# JonesHBridge.net
KiCad netlist of a schematic drawn in EAGLE
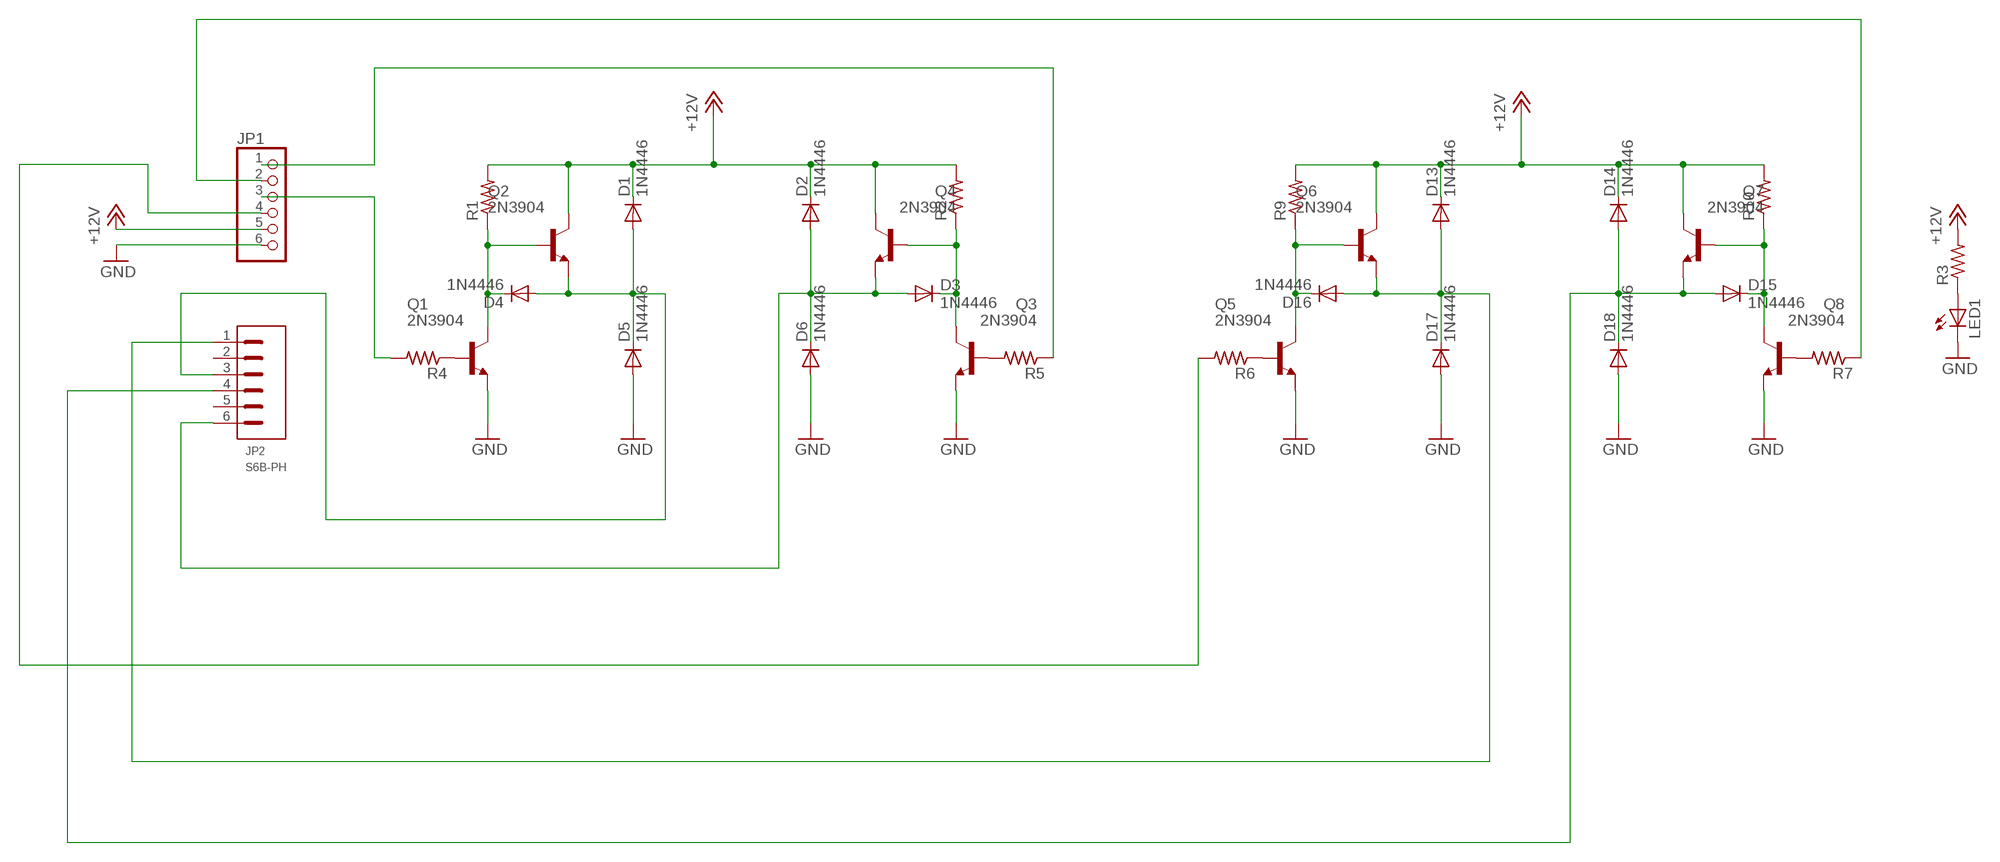
[diagram p0: schematic, sheet 1]

(export (version "E")
  (design (tool "Eeschema 10.0.6"))
  (components
    (comp (ref "D1")
      (value "1N4446")
      (footprint "eagle-import:DO35-10")
      (libsource (lib "eagle-import") (part "1N4446"))
    )
    (comp (ref "D2")
      (value "1N4446")
      (footprint "eagle-import:DO35-10")
      (libsource (lib "eagle-import") (part "1N4446"))
    )
    (comp (ref "D3")
      (value "1N4446")
      (footprint "eagle-import:DO35-10")
      (libsource (lib "eagle-import") (part "1N4446"))
    )
    (comp (ref "D4")
      (value "1N4446")
      (footprint "eagle-import:DO35-10")
      (libsource (lib "eagle-import") (part "1N4446"))
    )
    (comp (ref "D5")
      (value "1N4446")
      (footprint "eagle-import:DO35-10")
      (libsource (lib "eagle-import") (part "1N4446"))
    )
    (comp (ref "D6")
      (value "1N4446")
      (footprint "eagle-import:DO35-10")
      (libsource (lib "eagle-import") (part "1N4446"))
    )
    (comp (ref "D13")
      (value "1N4446")
      (footprint "eagle-import:DO35-10")
      (libsource (lib "eagle-import") (part "1N4446"))
    )
    (comp (ref "D14")
      (value "1N4446")
      (footprint "eagle-import:DO35-10")
      (libsource (lib "eagle-import") (part "1N4446"))
    )
    (comp (ref "D15")
      (value "1N4446")
      (footprint "eagle-import:DO35-10")
      (libsource (lib "eagle-import") (part "1N4446"))
    )
    (comp (ref "D16")
      (value "1N4446")
      (footprint "eagle-import:DO35-10")
      (libsource (lib "eagle-import") (part "1N4446"))
    )
    (comp (ref "D17")
      (value "1N4446")
      (footprint "eagle-import:DO35-10")
      (libsource (lib "eagle-import") (part "1N4446"))
    )
    (comp (ref "D18")
      (value "1N4446")
      (footprint "eagle-import:DO35-10")
      (libsource (lib "eagle-import") (part "1N4446"))
    )
    (comp (ref "JP1")
      (value "PINHD-1X6")
      (footprint "eagle-import:1X06")
      (libsource (lib "eagle-import") (part "PINHD-1X6"))
    )
    (comp (ref "JP2")
      (value "S6B-PH")
      (footprint "eagle-import:S6B")
      (libsource (lib "eagle-import") (part "S6B-PH"))
    )
    (comp (ref "LED1")
      (value "LED3MM")
      (footprint "eagle-import:LED3MM")
      (libsource (lib "eagle-import") (part "LED3MM"))
    )
    (comp (ref "Q1")
      (value "2N3904")
      (footprint "eagle-import:TO92")
      (libsource (lib "eagle-import") (part "2N3904"))
    )
    (comp (ref "Q2")
      (value "2N3904")
      (footprint "eagle-import:TO92")
      (libsource (lib "eagle-import") (part "2N3904"))
    )
    (comp (ref "Q3")
      (value "2N3904")
      (footprint "eagle-import:TO92")
      (libsource (lib "eagle-import") (part "2N3904"))
    )
    (comp (ref "Q4")
      (value "2N3904")
      (footprint "eagle-import:TO92")
      (libsource (lib "eagle-import") (part "2N3904"))
    )
    (comp (ref "Q5")
      (value "2N3904")
      (footprint "eagle-import:TO92")
      (libsource (lib "eagle-import") (part "2N3904"))
    )
    (comp (ref "Q6")
      (value "2N3904")
      (footprint "eagle-import:TO92")
      (libsource (lib "eagle-import") (part "2N3904"))
    )
    (comp (ref "Q7")
      (value "2N3904")
      (footprint "eagle-import:TO92")
      (libsource (lib "eagle-import") (part "2N3904"))
    )
    (comp (ref "Q8")
      (value "2N3904")
      (footprint "eagle-import:TO92")
      (libsource (lib "eagle-import") (part "2N3904"))
    )
    (comp (ref "R1")
      (value "R-US_R0805")
      (footprint "eagle-import:R0805")
      (libsource (lib "eagle-import") (part "R-US_R0805"))
    )
    (comp (ref "R2")
      (value "R-US_R0805")
      (footprint "eagle-import:R0805")
      (libsource (lib "eagle-import") (part "R-US_R0805"))
    )
    (comp (ref "R3")
      (value "R-US_R0805")
      (footprint "eagle-import:R0805")
      (libsource (lib "eagle-import") (part "R-US_R0805"))
    )
    (comp (ref "R4")
      (value "R-US_R0805")
      (footprint "eagle-import:R0805")
      (libsource (lib "eagle-import") (part "R-US_R0805"))
    )
    (comp (ref "R5")
      (value "R-US_R0805")
      (footprint "eagle-import:R0805")
      (libsource (lib "eagle-import") (part "R-US_R0805"))
    )
    (comp (ref "R6")
      (value "R-US_R0805")
      (footprint "eagle-import:R0805")
      (libsource (lib "eagle-import") (part "R-US_R0805"))
    )
    (comp (ref "R7")
      (value "R-US_R0805")
      (footprint "eagle-import:R0805")
      (libsource (lib "eagle-import") (part "R-US_R0805"))
    )
    (comp (ref "R9")
      (value "R-US_R0805")
      (footprint "eagle-import:R0805")
      (libsource (lib "eagle-import") (part "R-US_R0805"))
    )
    (comp (ref "R10")
      (value "R-US_R0805")
      (footprint "eagle-import:R0805")
      (libsource (lib "eagle-import") (part "R-US_R0805"))
    )
  )
  (nets
    (net (code "1") (name "+12V") (class "Default")
      (node (ref "D1") (pin "C") (pinfunction "C_C") (pintype "passive"))
      (node (ref "D13") (pin "C") (pinfunction "C_C") (pintype "passive"))
      (node (ref "D14") (pin "C") (pinfunction "C_C") (pintype "passive"))
      (node (ref "D2") (pin "C") (pinfunction "C_C") (pintype "passive"))
      (node (ref "JP1") (pin "5") (pinfunction "5_5") (pintype "passive"))
      (node (ref "Q2") (pin "1") (pinfunction "C_1") (pintype "passive"))
      (node (ref "Q4") (pin "1") (pinfunction "C_1") (pintype "passive"))
      (node (ref "Q6") (pin "1") (pinfunction "C_1") (pintype "passive"))
      (node (ref "Q7") (pin "1") (pinfunction "C_1") (pintype "passive"))
      (node (ref "R1") (pin "2") (pinfunction "2_2") (pintype "passive"))
      (node (ref "R10") (pin "2") (pinfunction "2_2") (pintype "passive"))
      (node (ref "R2") (pin "2") (pinfunction "2_2") (pintype "passive"))
      (node (ref "R3") (pin "2") (pinfunction "2_2") (pintype "passive"))
      (node (ref "R9") (pin "2") (pinfunction "2_2") (pintype "passive"))
    )
    (net (code "2") (name "GND") (class "Default")
      (node (ref "D17") (pin "A") (pinfunction "A_A") (pintype "passive"))
      (node (ref "D18") (pin "A") (pinfunction "A_A") (pintype "passive"))
      (node (ref "D5") (pin "A") (pinfunction "A_A") (pintype "passive"))
      (node (ref "D6") (pin "A") (pinfunction "A_A") (pintype "passive"))
      (node (ref "JP1") (pin "6") (pinfunction "6_6") (pintype "passive"))
      (node (ref "LED1") (pin "K") (pinfunction "C_K") (pintype "passive"))
      (node (ref "Q1") (pin "3") (pinfunction "E_3") (pintype "passive"))
      (node (ref "Q3") (pin "3") (pinfunction "E_3") (pintype "passive"))
      (node (ref "Q5") (pin "3") (pinfunction "E_3") (pintype "passive"))
      (node (ref "Q8") (pin "3") (pinfunction "E_3") (pintype "passive"))
    )
    (net (code "3") (name "Net-(JP1-Pad1)") (class "Default")
      (node (ref "JP1") (pin "1") (pinfunction "1_1") (pintype "passive"))
      (node (ref "R5") (pin "1") (pinfunction "1_1") (pintype "passive"))
    )
    (net (code "4") (name "Net-(JP1-Pad2)") (class "Default")
      (node (ref "JP1") (pin "2") (pinfunction "2_2") (pintype "passive"))
      (node (ref "R7") (pin "1") (pinfunction "1_1") (pintype "passive"))
    )
    (net (code "5") (name "Net-(JP1-Pad3)") (class "Default")
      (node (ref "JP1") (pin "3") (pinfunction "3_3") (pintype "passive"))
      (node (ref "R4") (pin "2") (pinfunction "2_2") (pintype "passive"))
    )
    (net (code "6") (name "Net-(JP1-Pad4)") (class "Default")
      (node (ref "JP1") (pin "4") (pinfunction "4_4") (pintype "passive"))
      (node (ref "R6") (pin "2") (pinfunction "2_2") (pintype "passive"))
    )
    (net (code "7") (name "Net-(LED1-PadA)") (class "Default")
      (node (ref "LED1") (pin "A") (pinfunction "A_A") (pintype "passive"))
      (node (ref "R3") (pin "1") (pinfunction "1_1") (pintype "passive"))
    )
    (net (code "8") (name "Net-(Q1-B)") (class "Default")
      (node (ref "Q1") (pin "2") (pinfunction "B_2") (pintype "passive"))
      (node (ref "R4") (pin "1") (pinfunction "1_1") (pintype "passive"))
    )
    (net (code "9") (name "Net-(Q1-C)") (class "Default")
      (node (ref "D4") (pin "C") (pinfunction "C_C") (pintype "passive"))
      (node (ref "Q1") (pin "1") (pinfunction "C_1") (pintype "passive"))
      (node (ref "Q2") (pin "2") (pinfunction "B_2") (pintype "passive"))
      (node (ref "R1") (pin "1") (pinfunction "1_1") (pintype "passive"))
    )
    (net (code "10") (name "Net-(Q2-E)") (class "Default")
      (node (ref "D1") (pin "A") (pinfunction "A_A") (pintype "passive"))
      (node (ref "D4") (pin "A") (pinfunction "A_A") (pintype "passive"))
      (node (ref "D5") (pin "C") (pinfunction "C_C") (pintype "passive"))
      (node (ref "JP2") (pin "3") (pinfunction "3_3") (pintype "bidirectional"))
      (node (ref "Q2") (pin "3") (pinfunction "E_3") (pintype "passive"))
    )
    (net (code "11") (name "Net-(Q3-B)") (class "Default")
      (node (ref "Q3") (pin "2") (pinfunction "B_2") (pintype "passive"))
      (node (ref "R5") (pin "2") (pinfunction "2_2") (pintype "passive"))
    )
    (net (code "12") (name "Net-(Q3-C)") (class "Default")
      (node (ref "D3") (pin "C") (pinfunction "C_C") (pintype "passive"))
      (node (ref "Q3") (pin "1") (pinfunction "C_1") (pintype "passive"))
      (node (ref "Q4") (pin "2") (pinfunction "B_2") (pintype "passive"))
      (node (ref "R2") (pin "1") (pinfunction "1_1") (pintype "passive"))
    )
    (net (code "13") (name "Net-(Q4-E)") (class "Default")
      (node (ref "D2") (pin "A") (pinfunction "A_A") (pintype "passive"))
      (node (ref "D3") (pin "A") (pinfunction "A_A") (pintype "passive"))
      (node (ref "D6") (pin "C") (pinfunction "C_C") (pintype "passive"))
      (node (ref "JP2") (pin "6") (pinfunction "6_6") (pintype "bidirectional"))
      (node (ref "Q4") (pin "3") (pinfunction "E_3") (pintype "passive"))
    )
    (net (code "14") (name "Net-(Q5-B)") (class "Default")
      (node (ref "Q5") (pin "2") (pinfunction "B_2") (pintype "passive"))
      (node (ref "R6") (pin "1") (pinfunction "1_1") (pintype "passive"))
    )
    (net (code "15") (name "Net-(Q5-C)") (class "Default")
      (node (ref "D16") (pin "C") (pinfunction "C_C") (pintype "passive"))
      (node (ref "Q5") (pin "1") (pinfunction "C_1") (pintype "passive"))
      (node (ref "Q6") (pin "2") (pinfunction "B_2") (pintype "passive"))
      (node (ref "R9") (pin "1") (pinfunction "1_1") (pintype "passive"))
    )
    (net (code "16") (name "Net-(Q6-E)") (class "Default")
      (node (ref "D13") (pin "A") (pinfunction "A_A") (pintype "passive"))
      (node (ref "D16") (pin "A") (pinfunction "A_A") (pintype "passive"))
      (node (ref "D17") (pin "C") (pinfunction "C_C") (pintype "passive"))
      (node (ref "JP2") (pin "1") (pinfunction "1_1") (pintype "bidirectional"))
      (node (ref "Q6") (pin "3") (pinfunction "E_3") (pintype "passive"))
    )
    (net (code "17") (name "Net-(Q7-B)") (class "Default")
      (node (ref "D15") (pin "C") (pinfunction "C_C") (pintype "passive"))
      (node (ref "Q7") (pin "2") (pinfunction "B_2") (pintype "passive"))
      (node (ref "Q8") (pin "1") (pinfunction "C_1") (pintype "passive"))
      (node (ref "R10") (pin "1") (pinfunction "1_1") (pintype "passive"))
    )
    (net (code "18") (name "Net-(Q7-E)") (class "Default")
      (node (ref "D14") (pin "A") (pinfunction "A_A") (pintype "passive"))
      (node (ref "D15") (pin "A") (pinfunction "A_A") (pintype "passive"))
      (node (ref "D18") (pin "C") (pinfunction "C_C") (pintype "passive"))
      (node (ref "JP2") (pin "4") (pinfunction "4_4") (pintype "bidirectional"))
      (node (ref "Q7") (pin "3") (pinfunction "E_3") (pintype "passive"))
    )
    (net (code "19") (name "Net-(Q8-B)") (class "Default")
      (node (ref "Q8") (pin "2") (pinfunction "B_2") (pintype "passive"))
      (node (ref "R7") (pin "2") (pinfunction "2_2") (pintype "passive"))
    )
    (net (code "20") (name "unconnected-(JP2-Pad2)") (class "Default")
      (node (ref "JP2") (pin "2") (pinfunction "2_2") (pintype "bidirectional"))
    )
    (net (code "21") (name "unconnected-(JP2-Pad5)") (class "Default")
      (node (ref "JP2") (pin "5") (pinfunction "5_5") (pintype "bidirectional"))
    )
  )
)
